# zikzak3-modules-gpu.net
KiCad netlist of a schematic drawn in EAGLE
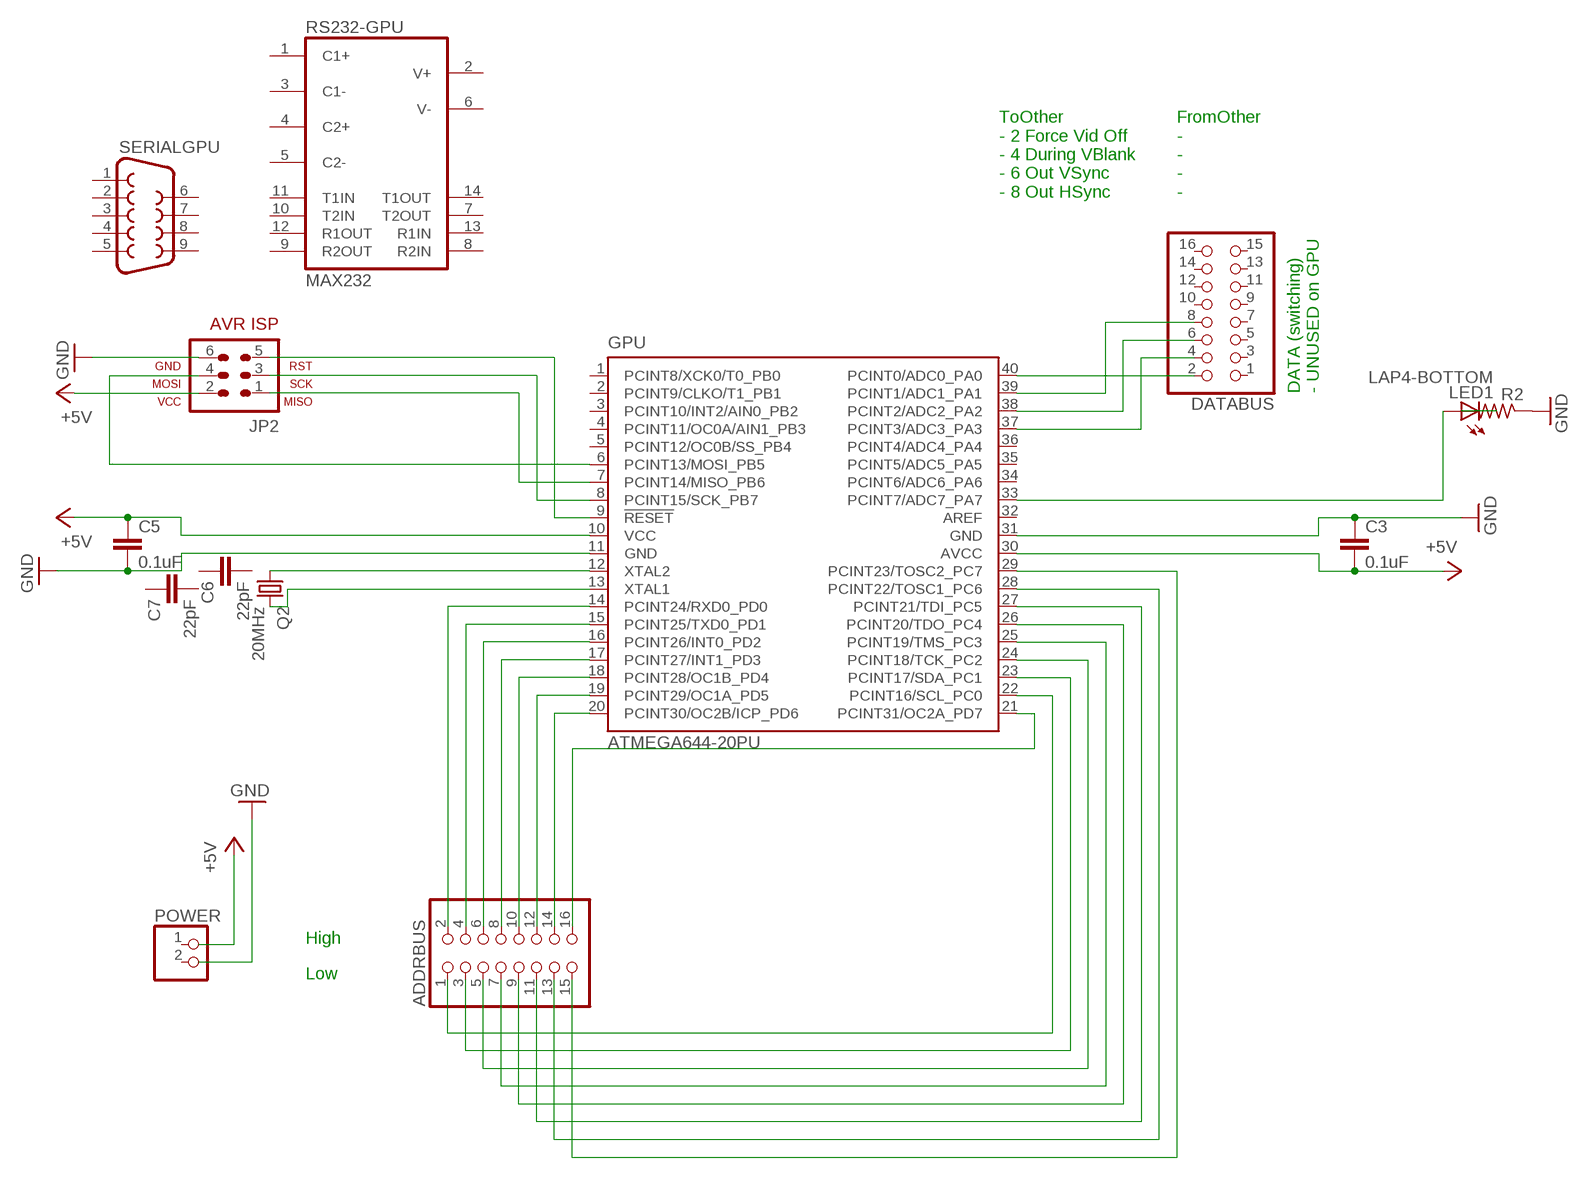
[diagram p0: schematic, sheet 1]

(export (version "E")
  (design (tool "Eeschema 10.0.6"))
  (components
    (comp (ref "ADDRBUS")
      (value "PINHD-2X8/90")
      (footprint "eagle-import:2X08_90")
      (libsource (lib "eagle-import") (part "PINHD-2X8/90"))
    )
    (comp (ref "C3")
      (value "0.1uF")
      (footprint "eagle-import:C2.5-3")
      (libsource (lib "eagle-import") (part "C2,5-3"))
    )
    (comp (ref "C5")
      (value "0.1uF")
      (footprint "eagle-import:C2.5-3")
      (libsource (lib "eagle-import") (part "C2,5-3"))
    )
    (comp (ref "C6")
      (value "22pF")
      (footprint "eagle-import:C2.5-3")
      (libsource (lib "eagle-import") (part "C2,5-3"))
    )
    (comp (ref "C7")
      (value "22pF")
      (footprint "eagle-import:C2.5-3")
      (libsource (lib "eagle-import") (part "C2,5-3"))
    )
    (comp (ref "DATABUS")
      (value "PINHD-2X8/90")
      (footprint "eagle-import:2X08_90")
      (libsource (lib "eagle-import") (part "PINHD-2X8/90"))
    )
    (comp (ref "GPU")
      (value "ATMEGA644-20PU")
      (footprint "eagle-import:DIL40")
      (libsource (lib "eagle-import") (part "ATMEGA644-PU20"))
    )
    (comp (ref "JP2")
      (value "AVR-ISP-6VERT")
      (footprint "eagle-import:AVR-ISP-6")
      (libsource (lib "eagle-import") (part "AVR-ISP-6VERT"))
    )
    (comp (ref "LED1")
      (value "LAP4-BOTTOM")
      (footprint "eagle-import:P47F-BOTTOM")
      (libsource (lib "eagle-import") (part "P4-BOTTOMLA"))
    )
    (comp (ref "POWER")
      (value "PINHD-1X2")
      (footprint "eagle-import:1X02")
      (libsource (lib "eagle-import") (part "PINHD-1X2"))
    )
    (comp (ref "Q2")
      (value "20MHz")
      (footprint "eagle-import:TC38H")
      (libsource (lib "eagle-import") (part "CRYSTALTC38H"))
    )
    (comp (ref "R2")
      (value "R-US_0204/2V")
      (footprint "eagle-import:0204V")
      (libsource (lib "eagle-import") (part "R-US_0204/2V"))
    )
    (comp (ref "RS232-GPU")
      (value "MAX232")
      (footprint "eagle-import:DIL16")
      (fields (field (name "MF") "MAXIM") (field (name "MPN") "MAX232ACPE+"))
      (libsource (lib "eagle-import") (part "MAX232"))
    )
    (comp (ref "SERIALGPU")
      (value "F09H")
      (footprint "eagle-import:F09H")
      (libsource (lib "eagle-import") (part "F09H"))
    )
  )
  (nets
    (net (code "1") (name "+5V") (class "Default")
      (node (ref "C3") (pin "2") (pinfunction "2_2") (pintype "passive"))
      (node (ref "C5") (pin "1") (pinfunction "1_1") (pintype "passive"))
      (node (ref "GPU") (pin "10") (pinfunction "VCC_10") (pintype "power_in"))
      (node (ref "GPU") (pin "30") (pinfunction "AVCC_30") (pintype "power_in"))
      (node (ref "JP2") (pin "2") (pinfunction "2_2") (pintype "passive"))
    )
    (net (code "2") (name "GND") (class "Default")
      (node (ref "C3") (pin "1") (pinfunction "1_1") (pintype "passive"))
      (node (ref "C5") (pin "2") (pinfunction "2_2") (pintype "passive"))
      (node (ref "GPU") (pin "11") (pinfunction "GND_11") (pintype "power_in"))
      (node (ref "GPU") (pin "31") (pinfunction "GND_31") (pintype "power_in"))
      (node (ref "JP2") (pin "6") (pinfunction "6_6") (pintype "passive"))
      (node (ref "R2") (pin "1") (pinfunction "1_1") (pintype "passive"))
    )
    (net (code "3") (name "Net-(GPU-PCINT0{slash}ADC0_PA0)") (class "Default")
      (node (ref "DATABUS") (pin "2") (pinfunction "2_2") (pintype "passive"))
      (node (ref "GPU") (pin "40") (pinfunction "PCINT0/ADC0_PA0_40") (pintype "bidirectional"))
    )
    (net (code "4") (name "Net-(GPU-PCINT1{slash}ADC1_PA1)") (class "Default")
      (node (ref "DATABUS") (pin "8") (pinfunction "8_8") (pintype "passive"))
      (node (ref "GPU") (pin "39") (pinfunction "PCINT1/ADC1_PA1_39") (pintype "bidirectional"))
    )
    (net (code "5") (name "Net-(GPU-PCINT2{slash}ADC2_PA2)") (class "Default")
      (node (ref "DATABUS") (pin "6") (pinfunction "6_6") (pintype "passive"))
      (node (ref "GPU") (pin "38") (pinfunction "PCINT2/ADC2_PA2_38") (pintype "bidirectional"))
    )
    (net (code "6") (name "Net-(GPU-PCINT3{slash}ADC3_PA3)") (class "Default")
      (node (ref "DATABUS") (pin "4") (pinfunction "4_4") (pintype "passive"))
      (node (ref "GPU") (pin "37") (pinfunction "PCINT3/ADC3_PA3_37") (pintype "bidirectional"))
    )
    (net (code "7") (name "Net-(GPU-PCINT7{slash}ADC7_PA7)") (class "Default")
      (node (ref "GPU") (pin "33") (pinfunction "PCINT7/ADC7_PA7_33") (pintype "bidirectional"))
      (node (ref "LED1") (pin "A") (pinfunction "A_A") (pintype "passive"))
    )
    (net (code "8") (name "Net-(GPU-PCINT13{slash}MOSI_PB5)") (class "Default")
      (node (ref "GPU") (pin "6") (pinfunction "PCINT13/MOSI_PB5_6") (pintype "bidirectional"))
      (node (ref "JP2") (pin "4") (pinfunction "4_4") (pintype "passive"))
    )
    (net (code "9") (name "Net-(GPU-PCINT14{slash}MISO_PB6)") (class "Default")
      (node (ref "GPU") (pin "7") (pinfunction "PCINT14/MISO_PB6_7") (pintype "bidirectional"))
      (node (ref "JP2") (pin "1") (pinfunction "1_1") (pintype "passive"))
    )
    (net (code "10") (name "Net-(GPU-PCINT15{slash}SCK_PB7)") (class "Default")
      (node (ref "GPU") (pin "8") (pinfunction "PCINT15/SCK_PB7_8") (pintype "bidirectional"))
      (node (ref "JP2") (pin "3") (pinfunction "3_3") (pintype "passive"))
    )
    (net (code "11") (name "Net-(GPU-PCINT16{slash}SCL_PC0)") (class "Default")
      (node (ref "ADDRBUS") (pin "1") (pinfunction "1_1") (pintype "passive"))
      (node (ref "GPU") (pin "22") (pinfunction "PCINT16/SCL_PC0_22") (pintype "bidirectional"))
    )
    (net (code "12") (name "Net-(GPU-PCINT17{slash}SDA_PC1)") (class "Default")
      (node (ref "ADDRBUS") (pin "3") (pinfunction "3_3") (pintype "passive"))
      (node (ref "GPU") (pin "23") (pinfunction "PCINT17/SDA_PC1_23") (pintype "bidirectional"))
    )
    (net (code "13") (name "Net-(GPU-PCINT18{slash}TCK_PC2)") (class "Default")
      (node (ref "ADDRBUS") (pin "5") (pinfunction "5_5") (pintype "passive"))
      (node (ref "GPU") (pin "24") (pinfunction "PCINT18/TCK_PC2_24") (pintype "bidirectional"))
    )
    (net (code "14") (name "Net-(GPU-PCINT19{slash}TMS_PC3)") (class "Default")
      (node (ref "ADDRBUS") (pin "7") (pinfunction "7_7") (pintype "passive"))
      (node (ref "GPU") (pin "25") (pinfunction "PCINT19/TMS_PC3_25") (pintype "bidirectional"))
    )
    (net (code "15") (name "Net-(GPU-PCINT20{slash}TDO_PC4)") (class "Default")
      (node (ref "ADDRBUS") (pin "9") (pinfunction "9_9") (pintype "passive"))
      (node (ref "GPU") (pin "26") (pinfunction "PCINT20/TDO_PC4_26") (pintype "bidirectional"))
    )
    (net (code "16") (name "Net-(GPU-PCINT21{slash}TDI_PC5)") (class "Default")
      (node (ref "ADDRBUS") (pin "11") (pinfunction "11_11") (pintype "passive"))
      (node (ref "GPU") (pin "27") (pinfunction "PCINT21/TDI_PC5_27") (pintype "bidirectional"))
    )
    (net (code "17") (name "Net-(GPU-PCINT22{slash}TOSC1_PC6)") (class "Default")
      (node (ref "ADDRBUS") (pin "13") (pinfunction "13_13") (pintype "passive"))
      (node (ref "GPU") (pin "28") (pinfunction "PCINT22/TOSC1_PC6_28") (pintype "bidirectional"))
    )
    (net (code "18") (name "Net-(GPU-PCINT23{slash}TOSC2_PC7)") (class "Default")
      (node (ref "ADDRBUS") (pin "15") (pinfunction "15_15") (pintype "passive"))
      (node (ref "GPU") (pin "29") (pinfunction "PCINT23/TOSC2_PC7_29") (pintype "bidirectional"))
    )
    (net (code "19") (name "Net-(GPU-PCINT24{slash}RXD0_PD0)") (class "Default")
      (node (ref "ADDRBUS") (pin "2") (pinfunction "2_2") (pintype "passive"))
      (node (ref "GPU") (pin "14") (pinfunction "PCINT24/RXD0_PD0_14") (pintype "bidirectional"))
    )
    (net (code "20") (name "Net-(GPU-PCINT25{slash}TXD0_PD1)") (class "Default")
      (node (ref "ADDRBUS") (pin "4") (pinfunction "4_4") (pintype "passive"))
      (node (ref "GPU") (pin "15") (pinfunction "PCINT25/TXD0_PD1_15") (pintype "bidirectional"))
    )
    (net (code "21") (name "Net-(GPU-PCINT26{slash}INT0_PD2)") (class "Default")
      (node (ref "ADDRBUS") (pin "6") (pinfunction "6_6") (pintype "passive"))
      (node (ref "GPU") (pin "16") (pinfunction "PCINT26/INT0_PD2_16") (pintype "bidirectional"))
    )
    (net (code "22") (name "Net-(GPU-PCINT27{slash}INT1_PD3)") (class "Default")
      (node (ref "ADDRBUS") (pin "8") (pinfunction "8_8") (pintype "passive"))
      (node (ref "GPU") (pin "17") (pinfunction "PCINT27/INT1_PD3_17") (pintype "bidirectional"))
    )
    (net (code "23") (name "Net-(GPU-PCINT28{slash}OC1B_PD4)") (class "Default")
      (node (ref "ADDRBUS") (pin "10") (pinfunction "10_10") (pintype "passive"))
      (node (ref "GPU") (pin "18") (pinfunction "PCINT28/OC1B_PD4_18") (pintype "bidirectional"))
    )
    (net (code "24") (name "Net-(GPU-PCINT29{slash}OC1A_PD5)") (class "Default")
      (node (ref "ADDRBUS") (pin "12") (pinfunction "12_12") (pintype "passive"))
      (node (ref "GPU") (pin "19") (pinfunction "PCINT29/OC1A_PD5_19") (pintype "bidirectional"))
    )
    (net (code "25") (name "Net-(GPU-PCINT30{slash}OC2B{slash}ICP_PD6)") (class "Default")
      (node (ref "ADDRBUS") (pin "14") (pinfunction "14_14") (pintype "passive"))
      (node (ref "GPU") (pin "20") (pinfunction "PCINT30/OC2B/ICP_PD6_20") (pintype "bidirectional"))
    )
    (net (code "26") (name "Net-(GPU-PCINT31{slash}OC2A_PD7)") (class "Default")
      (node (ref "ADDRBUS") (pin "16") (pinfunction "16_16") (pintype "passive"))
      (node (ref "GPU") (pin "21") (pinfunction "PCINT31/OC2A_PD7_21") (pintype "bidirectional"))
    )
    (net (code "27") (name "Net-(GPU-XTAL1)") (class "Default")
      (node (ref "GPU") (pin "13") (pinfunction "XTAL1_13") (pintype "input"))
      (node (ref "Q2") (pin "2") (pinfunction "2_2") (pintype "passive"))
    )
    (net (code "28") (name "Net-(GPU-XTAL2)") (class "Default")
      (node (ref "GPU") (pin "12") (pinfunction "XTAL2_12") (pintype "output"))
      (node (ref "Q2") (pin "1") (pinfunction "1_1") (pintype "passive"))
    )
    (net (code "29") (name "Net-(GPU-~{RESET})") (class "Default")
      (node (ref "GPU") (pin "9") (pinfunction "~{RESET}_9") (pintype "input"))
      (node (ref "JP2") (pin "5") (pinfunction "5_5") (pintype "passive"))
    )
    (net (code "30") (name "Net-(LED1-PadC)") (class "Default")
      (node (ref "LED1") (pin "C") (pinfunction "C_C") (pintype "passive"))
      (node (ref "R2") (pin "2") (pinfunction "2_2") (pintype "passive"))
    )
    (net (code "31") (name "unconnected-(C6-Pad1)") (class "Default")
      (node (ref "C6") (pin "1") (pinfunction "1_1") (pintype "passive"))
    )
    (net (code "32") (name "unconnected-(C6-Pad2)") (class "Default")
      (node (ref "C6") (pin "2") (pinfunction "2_2") (pintype "passive"))
    )
    (net (code "33") (name "unconnected-(C7-Pad1)") (class "Default")
      (node (ref "C7") (pin "1") (pinfunction "1_1") (pintype "passive"))
    )
    (net (code "34") (name "unconnected-(C7-Pad2)") (class "Default")
      (node (ref "C7") (pin "2") (pinfunction "2_2") (pintype "passive"))
    )
    (net (code "35") (name "unconnected-(DATABUS-Pad1)") (class "Default")
      (node (ref "DATABUS") (pin "1") (pinfunction "1_1") (pintype "passive"))
    )
    (net (code "36") (name "unconnected-(DATABUS-Pad3)") (class "Default")
      (node (ref "DATABUS") (pin "3") (pinfunction "3_3") (pintype "passive"))
    )
    (net (code "37") (name "unconnected-(DATABUS-Pad5)") (class "Default")
      (node (ref "DATABUS") (pin "5") (pinfunction "5_5") (pintype "passive"))
    )
    (net (code "38") (name "unconnected-(DATABUS-Pad7)") (class "Default")
      (node (ref "DATABUS") (pin "7") (pinfunction "7_7") (pintype "passive"))
    )
    (net (code "39") (name "unconnected-(DATABUS-Pad9)") (class "Default")
      (node (ref "DATABUS") (pin "9") (pinfunction "9_9") (pintype "passive"))
    )
    (net (code "40") (name "unconnected-(DATABUS-Pad10)") (class "Default")
      (node (ref "DATABUS") (pin "10") (pinfunction "10_10") (pintype "passive"))
    )
    (net (code "41") (name "unconnected-(DATABUS-Pad11)") (class "Default")
      (node (ref "DATABUS") (pin "11") (pinfunction "11_11") (pintype "passive"))
    )
    (net (code "42") (name "unconnected-(DATABUS-Pad12)") (class "Default")
      (node (ref "DATABUS") (pin "12") (pinfunction "12_12") (pintype "passive"))
    )
    (net (code "43") (name "unconnected-(DATABUS-Pad13)") (class "Default")
      (node (ref "DATABUS") (pin "13") (pinfunction "13_13") (pintype "passive"))
    )
    (net (code "44") (name "unconnected-(DATABUS-Pad14)") (class "Default")
      (node (ref "DATABUS") (pin "14") (pinfunction "14_14") (pintype "passive"))
    )
    (net (code "45") (name "unconnected-(DATABUS-Pad15)") (class "Default")
      (node (ref "DATABUS") (pin "15") (pinfunction "15_15") (pintype "passive"))
    )
    (net (code "46") (name "unconnected-(DATABUS-Pad16)") (class "Default")
      (node (ref "DATABUS") (pin "16") (pinfunction "16_16") (pintype "passive"))
    )
    (net (code "47") (name "unconnected-(GPU-AREF-Pad32)") (class "Default")
      (node (ref "GPU") (pin "32") (pinfunction "AREF_32") (pintype "passive"))
    )
    (net (code "48") (name "unconnected-(GPU-PCINT4{slash}ADC4_PA4-Pad36)") (class "Default")
      (node (ref "GPU") (pin "36") (pinfunction "PCINT4/ADC4_PA4_36") (pintype "bidirectional"))
    )
    (net (code "49") (name "unconnected-(GPU-PCINT5{slash}ADC5_PA5-Pad35)") (class "Default")
      (node (ref "GPU") (pin "35") (pinfunction "PCINT5/ADC5_PA5_35") (pintype "bidirectional"))
    )
    (net (code "50") (name "unconnected-(GPU-PCINT6{slash}ADC6_PA6-Pad34)") (class "Default")
      (node (ref "GPU") (pin "34") (pinfunction "PCINT6/ADC6_PA6_34") (pintype "bidirectional"))
    )
    (net (code "51") (name "unconnected-(GPU-PCINT8{slash}XCK0{slash}T0_PB0-Pad1)") (class "Default")
      (node (ref "GPU") (pin "1") (pinfunction "PCINT8/XCK0/T0_PB0_1") (pintype "bidirectional"))
    )
    (net (code "52") (name "unconnected-(GPU-PCINT9{slash}CLKO{slash}T1_PB1-Pad2)") (class "Default")
      (node (ref "GPU") (pin "2") (pinfunction "PCINT9/CLKO/T1_PB1_2") (pintype "bidirectional"))
    )
    (net (code "53") (name "unconnected-(GPU-PCINT10{slash}INT2{slash}AIN0_PB2-Pad3)") (class "Default")
      (node (ref "GPU") (pin "3") (pinfunction "PCINT10/INT2/AIN0_PB2_3") (pintype "bidirectional"))
    )
    (net (code "54") (name "unconnected-(GPU-PCINT11{slash}OC0A{slash}AIN1_PB3-Pad4)") (class "Default")
      (node (ref "GPU") (pin "4") (pinfunction "PCINT11/OC0A/AIN1_PB3_4") (pintype "bidirectional"))
    )
    (net (code "55") (name "unconnected-(GPU-PCINT12{slash}OC0B{slash}SS_PB4-Pad5)") (class "Default")
      (node (ref "GPU") (pin "5") (pinfunction "PCINT12/OC0B/SS_PB4_5") (pintype "bidirectional"))
    )
    (net (code "56") (name "unconnected-(POWER-Pad1)") (class "Default")
      (node (ref "POWER") (pin "1") (pinfunction "1_1") (pintype "passive"))
    )
    (net (code "57") (name "unconnected-(POWER-Pad2)") (class "Default")
      (node (ref "POWER") (pin "2") (pinfunction "2_2") (pintype "passive"))
    )
    (net (code "58") (name "unconnected-(RS232-GPUA-C1+-Pad1)") (class "Default")
      (node (ref "RS232-GPU") (pin "1") (pinfunction "C1+_1") (pintype "bidirectional"))
    )
    (net (code "59") (name "unconnected-(RS232-GPUA-C1--Pad3)") (class "Default")
      (node (ref "RS232-GPU") (pin "3") (pinfunction "C1-_3") (pintype "bidirectional"))
    )
    (net (code "60") (name "unconnected-(RS232-GPUA-C2+-Pad4)") (class "Default")
      (node (ref "RS232-GPU") (pin "4") (pinfunction "C2+_4") (pintype "bidirectional"))
    )
    (net (code "61") (name "unconnected-(RS232-GPUA-C2--Pad5)") (class "Default")
      (node (ref "RS232-GPU") (pin "5") (pinfunction "C2-_5") (pintype "bidirectional"))
    )
    (net (code "62") (name "unconnected-(RS232-GPUA-R1IN-Pad13)") (class "Default")
      (node (ref "RS232-GPU") (pin "13") (pinfunction "R1IN_13") (pintype "input"))
    )
    (net (code "63") (name "unconnected-(RS232-GPUA-R1OUT-Pad12)") (class "Default")
      (node (ref "RS232-GPU") (pin "12") (pinfunction "R1OUT_12") (pintype "output"))
    )
    (net (code "64") (name "unconnected-(RS232-GPUA-R2IN-Pad8)") (class "Default")
      (node (ref "RS232-GPU") (pin "8") (pinfunction "R2IN_8") (pintype "input"))
    )
    (net (code "65") (name "unconnected-(RS232-GPUA-R2OUT-Pad9)") (class "Default")
      (node (ref "RS232-GPU") (pin "9") (pinfunction "R2OUT_9") (pintype "output"))
    )
    (net (code "66") (name "unconnected-(RS232-GPUA-T1IN-Pad11)") (class "Default")
      (node (ref "RS232-GPU") (pin "11") (pinfunction "T1IN_11") (pintype "input"))
    )
    (net (code "67") (name "unconnected-(RS232-GPUA-T1OUT-Pad14)") (class "Default")
      (node (ref "RS232-GPU") (pin "14") (pinfunction "T1OUT_14") (pintype "output"))
    )
    (net (code "68") (name "unconnected-(RS232-GPUA-T2IN-Pad10)") (class "Default")
      (node (ref "RS232-GPU") (pin "10") (pinfunction "T2IN_10") (pintype "input"))
    )
    (net (code "69") (name "unconnected-(RS232-GPUA-T2OUT-Pad7)") (class "Default")
      (node (ref "RS232-GPU") (pin "7") (pinfunction "T2OUT_7") (pintype "output"))
    )
    (net (code "70") (name "unconnected-(RS232-GPUA-V+-Pad2)") (class "Default")
      (node (ref "RS232-GPU") (pin "2") (pinfunction "V+_2") (pintype "bidirectional"))
    )
    (net (code "71") (name "unconnected-(RS232-GPUA-V--Pad6)") (class "Default")
      (node (ref "RS232-GPU") (pin "6") (pinfunction "V-_6") (pintype "bidirectional"))
    )
    (net (code "72") (name "unconnected-(SERIALGPU-Pad1)") (class "Default")
      (node (ref "SERIALGPU") (pin "1") (pinfunction "1_1") (pintype "passive"))
    )
    (net (code "73") (name "unconnected-(SERIALGPU-Pad2)") (class "Default")
      (node (ref "SERIALGPU") (pin "2") (pinfunction "2_2") (pintype "passive"))
    )
    (net (code "74") (name "unconnected-(SERIALGPU-Pad3)") (class "Default")
      (node (ref "SERIALGPU") (pin "3") (pinfunction "3_3") (pintype "passive"))
    )
    (net (code "75") (name "unconnected-(SERIALGPU-Pad4)") (class "Default")
      (node (ref "SERIALGPU") (pin "4") (pinfunction "4_4") (pintype "passive"))
    )
    (net (code "76") (name "unconnected-(SERIALGPU-Pad5)") (class "Default")
      (node (ref "SERIALGPU") (pin "5") (pinfunction "5_5") (pintype "passive"))
    )
    (net (code "77") (name "unconnected-(SERIALGPU-Pad6)") (class "Default")
      (node (ref "SERIALGPU") (pin "6") (pinfunction "6_6") (pintype "passive"))
    )
    (net (code "78") (name "unconnected-(SERIALGPU-Pad7)") (class "Default")
      (node (ref "SERIALGPU") (pin "7") (pinfunction "7_7") (pintype "passive"))
    )
    (net (code "79") (name "unconnected-(SERIALGPU-Pad8)") (class "Default")
      (node (ref "SERIALGPU") (pin "8") (pinfunction "8_8") (pintype "passive"))
    )
    (net (code "80") (name "unconnected-(SERIALGPU-Pad9)") (class "Default")
      (node (ref "SERIALGPU") (pin "9") (pinfunction "9_9") (pintype "passive"))
    )
  )
)
